# 16_-_PWR_2V5_1V5.net
KiCad netlist of a schematic drawn in Altium Designer
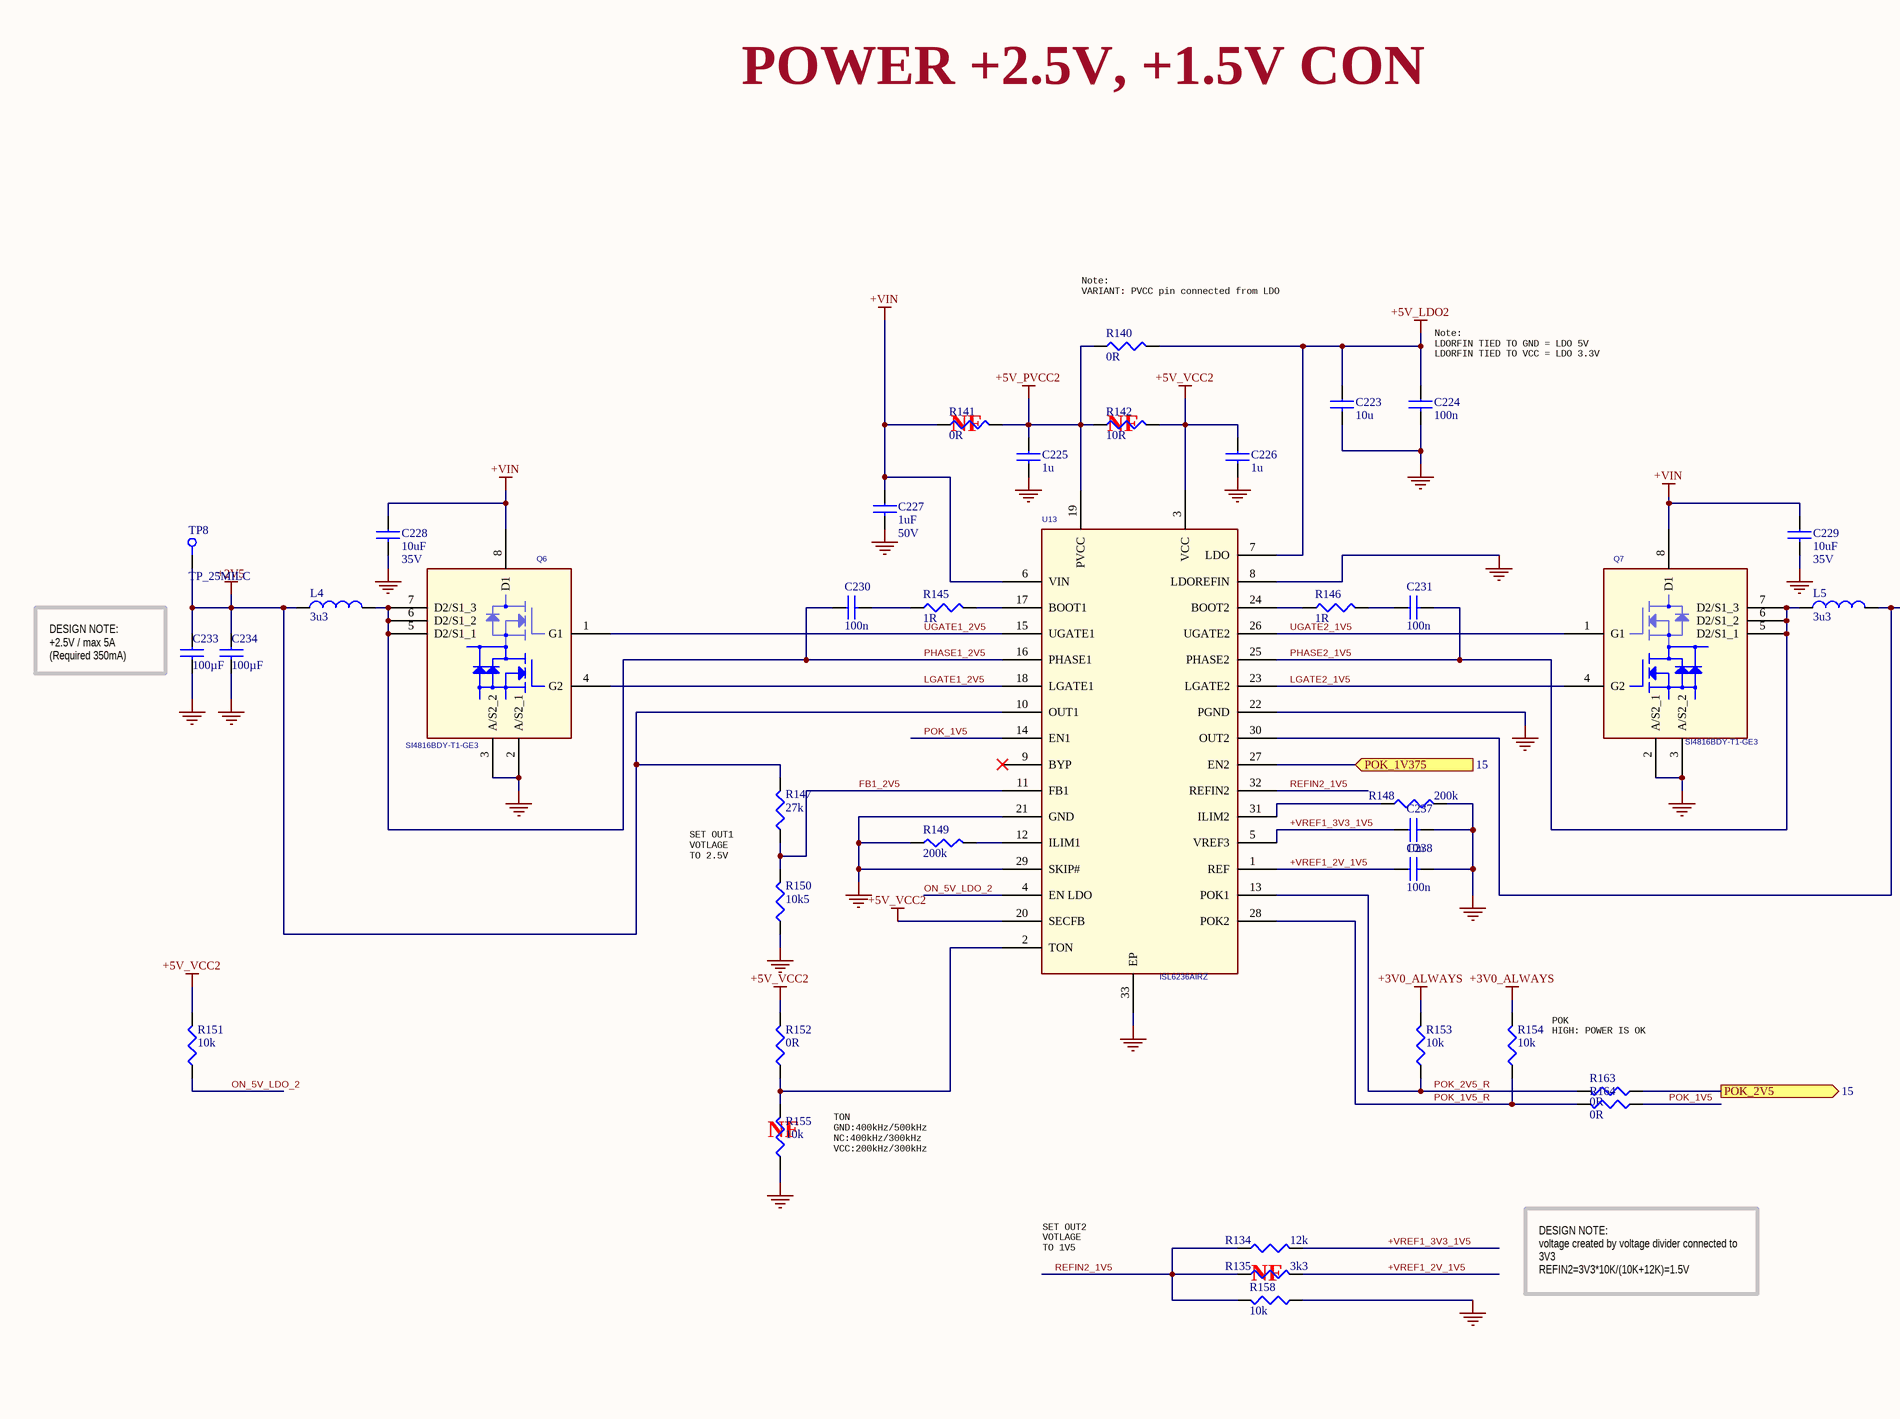
[diagram p0: [16] - PWR 2V5, 1V5.SchDoc, left]
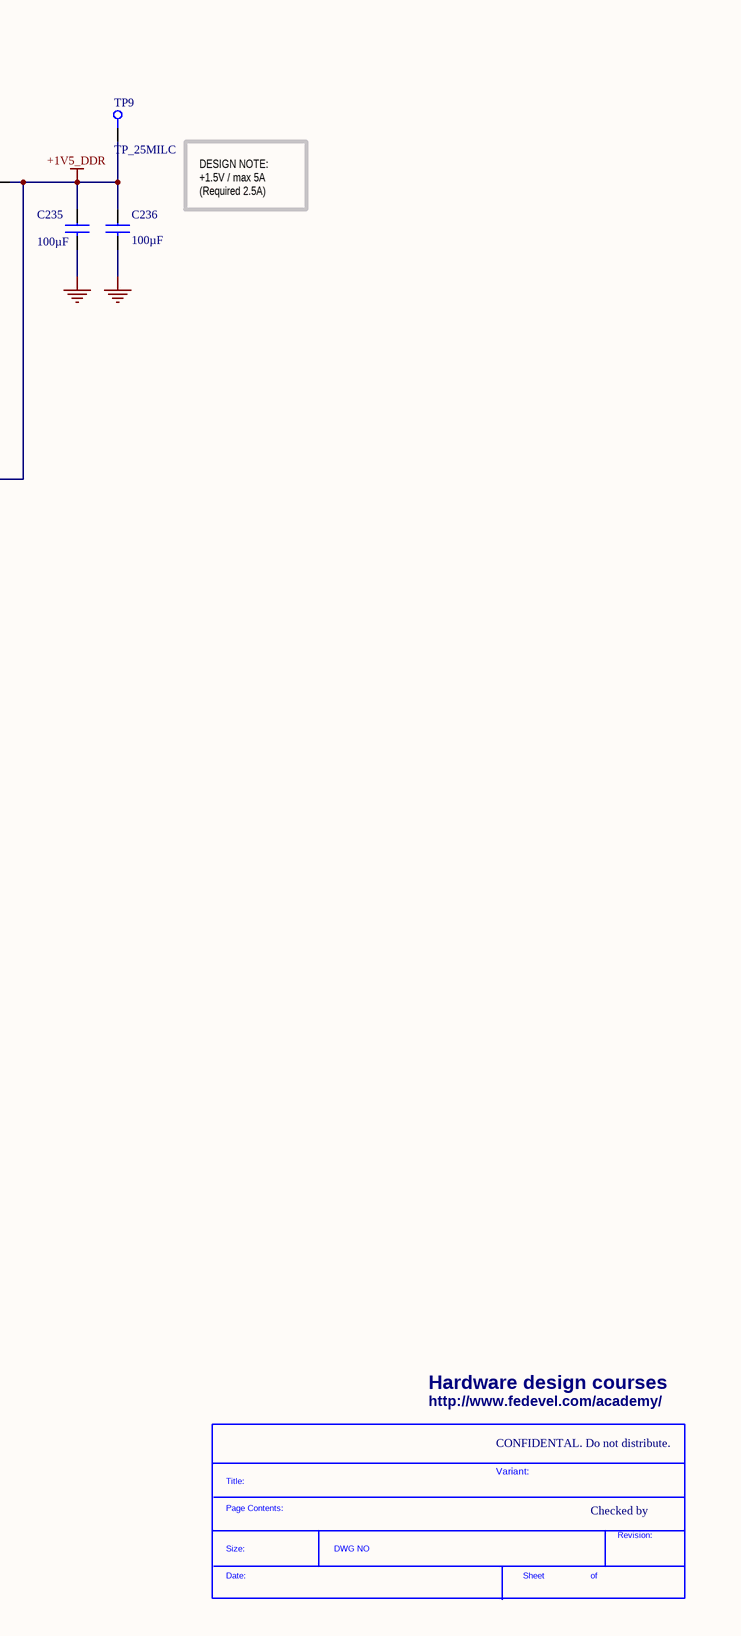
[diagram p1: [16] - PWR 2V5, 1V5.SchDoc, right]

(export (version "E")
  (design (tool "Eeschema 10.0.6"))
  (components
    (comp (ref "C223")
      (value "10u")
      (footprint "C0603")
      (description "CAP CER 10UF 6.3V X5R 20% 0603")
      (fields
        (field (name "MANUFACTURER") "TDK Corporation")
        (field (name "MANUFACTURER PART NUMBER") "C1608X5R0J106M")
      )
      (libsource (lib "iMX6 Rex_V1I1") (part "C1608X5R0J106M"))
    )
    (comp (ref "C224")
      (value "100n")
      (footprint "C0402")
      (description "CAP CER .10UF 50V X5R 10% 0402")
      (fields
        (field (name "MANUFACTURER") "TDK Corporation")
        (field (name "MANUFACTURER PART NUMBER") "C1005X5R1H104K")
      )
      (libsource (lib "iMX6 Rex_V1I1") (part "C1005X5R1H104K"))
    )
    (comp (ref "C225")
      (value "1u")
      (footprint "C0402")
      (description "CAP CER 1.0UF 16V X5R 0402")
      (fields
        (field (name "MANUFACTURER") "TDK Corporation")
        (field (name "MANUFACTURER PART NUMBER") "C1005X5R1C105K")
      )
      (libsource (lib "iMX6 Rex_V1I1") (part "C1005X5R1C105K"))
    )
    (comp (ref "C226")
      (value "1u")
      (footprint "C0402")
      (description "CAP CER 1.0UF 16V X5R 0402")
      (fields
        (field (name "MANUFACTURER") "TDK Corporation")
        (field (name "MANUFACTURER PART NUMBER") "C1005X5R1C105K")
      )
      (libsource (lib "iMX6 Rex_V1I1") (part "C1005X5R1C105K"))
    )
    (comp (ref "C227")
      (value "1uF")
      (footprint "C0805")
      (description "CAP CER 1UF 50V X7R 0805")
      (fields
        (field (name "MANUFACTURER") "Murata Electronics North America")
        (field (name "MANUFACTURER PART NUMBER") "GRM21BR71H105KA12L")
        (field (name "VOLTAGE - RATED") "50V")
      )
      (libsource (lib "iMX6 Rex_V1I1") (part "GRM21BR71H105KA12L"))
    )
    (comp (ref "C228")
      (value "10uF")
      (footprint "C1206")
      (description "CAP CER 10UF 35V X5R 1206")
      (fields
        (field (name "MANUFACTURER") "Murata Electronics North America")
        (field (name "MANUFACTURER PART NUMBER") "GRM31CR6YA106KA12L")
        (field (name "VOLTAGE - RATED") "35V")
      )
      (libsource (lib "iMX6 Rex_V1I1") (part "GRM31CR6YA106KA12L"))
    )
    (comp (ref "C229")
      (value "10uF")
      (footprint "C1206")
      (description "CAP CER 10UF 35V X5R 1206")
      (fields
        (field (name "MANUFACTURER") "Murata Electronics North America")
        (field (name "MANUFACTURER PART NUMBER") "GRM31CR6YA106KA12L")
        (field (name "VOLTAGE - RATED") "35V")
      )
      (libsource (lib "iMX6 Rex_V1I1") (part "GRM31CR6YA106KA12L"))
    )
    (comp (ref "C230")
      (value "100n")
      (footprint "C0402")
      (description "CAP CER .10UF 50V X5R 10% 0402")
      (fields
        (field (name "MANUFACTURER") "TDK Corporation")
        (field (name "MANUFACTURER PART NUMBER") "C1005X5R1H104K")
      )
      (libsource (lib "iMX6 Rex_V1I1") (part "C1005X5R1H104K"))
    )
    (comp (ref "C231")
      (value "100n")
      (footprint "C0402")
      (description "CAP CER .10UF 50V X5R 10% 0402")
      (fields
        (field (name "MANUFACTURER") "TDK Corporation")
        (field (name "MANUFACTURER PART NUMBER") "C1005X5R1H104K")
      )
      (libsource (lib "iMX6 Rex_V1I1") (part "C1005X5R1H104K"))
    )
    (comp (ref "C233")
      (value "100µF")
      (footprint "C1206")
      (description "CAP CER 100UF 10V X5R 20% 1206")
      (fields
        (field (name "MANUFACTURER") "TDK Corporation")
        (field (name "MANUFACTURER PART NUMBER") "C3216X5R1A107M")
      )
      (libsource (lib "iMX6 Rex_V1I1") (part "C3216X5R1A107M"))
    )
    (comp (ref "C234")
      (value "100µF")
      (footprint "C1206")
      (description "CAP CER 100UF 10V X5R 20% 1206")
      (fields
        (field (name "MANUFACTURER") "TDK Corporation")
        (field (name "MANUFACTURER PART NUMBER") "C3216X5R1A107M")
      )
      (libsource (lib "iMX6 Rex_V1I1") (part "C3216X5R1A107M"))
    )
    (comp (ref "C235")
      (value "100µF")
      (footprint "C1206")
      (description "CAP CER 100UF 10V X5R 20% 1206")
      (fields
        (field (name "MANUFACTURER") "TDK Corporation")
        (field (name "MANUFACTURER PART NUMBER") "C3216X5R1A107M")
      )
      (libsource (lib "iMX6 Rex_V1I1") (part "C3216X5R1A107M"))
    )
    (comp (ref "C236")
      (value "100µF")
      (footprint "C1206")
      (description "CAP CER 100UF 10V X5R 20% 1206")
      (fields
        (field (name "MANUFACTURER") "TDK Corporation")
        (field (name "MANUFACTURER PART NUMBER") "C3216X5R1A107M")
      )
      (libsource (lib "iMX6 Rex_V1I1") (part "C3216X5R1A107M"))
    )
    (comp (ref "C237")
      (value "10n")
      (footprint "C0402")
      (description "CAP CER 10000PF 16V X7R 10% 0402")
      (fields
        (field (name "MANUFACTURER") "TDK Corporation")
        (field (name "MANUFACTURER PART NUMBER") "C1005X7R1C103K")
      )
      (libsource (lib "iMX6 Rex_V1I1") (part "C1005X7R1C103K"))
    )
    (comp (ref "C238")
      (value "100n")
      (footprint "C0402")
      (description "CAP CER .10UF 50V X5R 10% 0402")
      (fields
        (field (name "MANUFACTURER") "TDK Corporation")
        (field (name "MANUFACTURER PART NUMBER") "C1005X5R1H104K")
      )
      (libsource (lib "iMX6 Rex_V1I1") (part "C1005X5R1H104K"))
    )
    (comp (ref "L4")
      (value "3u3")
      (footprint "IHLP_255MILx270MIL")
      (description "INDUCTOR POWER 3.3UH 6A SMD")
      (fields
        (field (name "MANUFACTURER") "Vishay Dale")
        (field (name "MANUFACTURER PART NUMBER") "IHLP2525CZER3R3M01")
        (field (name ".CHECKED PCB") "RF")
        (field (name ".CHECKED SCH") "RF")
      )
      (libsource (lib "iMX6 Rex_V1I1") (part "IHLP2525CZER3R3M01"))
    )
    (comp (ref "L5")
      (value "3u3")
      (footprint "IHLP_255MILx270MIL")
      (description "INDUCTOR POWER 3.3UH 6A SMD")
      (fields
        (field (name "MANUFACTURER") "Vishay Dale")
        (field (name "MANUFACTURER PART NUMBER") "IHLP2525CZER3R3M01")
        (field (name ".CHECKED PCB") "RF")
        (field (name ".CHECKED SCH") "RF")
      )
      (libsource (lib "iMX6 Rex_V1I1") (part "IHLP2525CZER3R3M01"))
    )
    (comp (ref "Q6")
      (value "SI4816BDY-T1-GE3")
      (footprint "8_SOIC_3.9MM")
      (description "MOSFET DL N-CH 30V 6.8A 8-SOIC")
      (fields (field (name "MANUFACTURER") "Vishay/Siliconix"))
      (libsource (lib "iMX6 Rex_V1I1") (part "SI4816BDY-T1-GE3"))
    )
    (comp (ref "Q7")
      (value "SI4816BDY-T1-GE3")
      (footprint "8_SOIC_3.9MM")
      (description "MOSFET DL N-CH 30V 6.8A 8-SOIC")
      (fields (field (name "MANUFACTURER") "Vishay/Siliconix"))
      (libsource (lib "iMX6 Rex_V1I1") (part "SI4816BDY-T1-GE3"))
    )
    (comp (ref "R134")
      (value "12k")
      (footprint "R0402")
      (description "RES 12.0K OHM 1/16W 1% 0402 SMD")
      (fields
        (field (name "MANUFACTURER") "Yageo")
        (field (name "MANUFACTURER PART NUMBER") "RC0402FR-0712KL")
      )
      (libsource (lib "iMX6 Rex_V1I1") (part "RC0402FR-0712KL"))
    )
    (comp (ref "R135")
      (value "3k3")
      (footprint "R0402")
      (description "RES 3.30K OHM 1/16W 1% 0402 SMD")
      (fields
        (field (name "MANUFACTURER") "Yageo")
        (field (name "MANUFACTURER PART NUMBER") "RC0402FR-073K3L")
      )
      (libsource (lib "iMX6 Rex_V1I1") (part "RC0402FR-073K3L"))
    )
    (comp (ref "R140")
      (value "0R")
      (footprint "R0402")
      (description "RES 0.0 OHM 1/16W 0402 SMD")
      (fields
        (field (name "MANUFACTURER") "Yageo")
        (field (name "MANUFACTURER PART NUMBER") "RC0402JR-070RL")
      )
      (libsource (lib "iMX6 Rex_V1I1") (part "RC0402JR-070RL"))
    )
    (comp (ref "R141")
      (value "0R")
      (footprint "R0402")
      (description "RES 0.0 OHM 1/16W 0402 SMD")
      (fields
        (field (name "MANUFACTURER") "Yageo")
        (field (name "MANUFACTURER PART NUMBER") "RC0402JR-070RL")
      )
      (libsource (lib "iMX6 Rex_V1I1") (part "RC0402JR-070RL"))
    )
    (comp (ref "R142")
      (value "10R")
      (footprint "R0402")
      (description "RES 10.0 OHM 1/16W 1% 0402 SMD")
      (fields
        (field (name "MANUFACTURER") "Yageo")
        (field (name "MANUFACTURER PART NUMBER") "RC0402FR-0710RL")
      )
      (libsource (lib "iMX6 Rex_V1I1") (part "RC0402FR-0710RL"))
    )
    (comp (ref "R145")
      (value "1R")
      (footprint "R0402")
      (description "RES 1.00 OHM 1/16W 1% 0402 SM")
      (fields
        (field (name "MANUFACTURER") "Yageo")
        (field (name "MANUFACTURER PART NUMBER") "RC0402FR-071RL")
      )
      (libsource (lib "iMX6 Rex_V1I1") (part "RC0402FR-071RL"))
    )
    (comp (ref "R146")
      (value "1R")
      (footprint "R0402")
      (description "RES 1.00 OHM 1/16W 1% 0402 SM")
      (fields
        (field (name "MANUFACTURER") "Yageo")
        (field (name "MANUFACTURER PART NUMBER") "RC0402FR-071RL")
      )
      (libsource (lib "iMX6 Rex_V1I1") (part "RC0402FR-071RL"))
    )
    (comp (ref "R147")
      (value "27k")
      (footprint "R0402")
      (description "RES 27.0K OHM 1/16W 1% 0402 SMD")
      (fields
        (field (name "MANUFACTURER") "Yageo")
        (field (name "MANUFACTURER PART NUMBER") "RC0402FR-0727KL")
        (field (name ".CHECKED PCB") "RF")
        (field (name ".CHECKED SCH") "RF")
      )
      (libsource (lib "iMX6 Rex_V1I1") (part "RC0402FR-0727KL"))
    )
    (comp (ref "R148")
      (value "200k")
      (footprint "R0402")
      (description "RES 200K OHM 1/16W 1% 0402 SMD")
      (fields
        (field (name "MANUFACTURER") "Yageo")
        (field (name "MANUFACTURER PART NUMBER") "RC0402FR-07200KL")
      )
      (libsource (lib "iMX6 Rex_V1I1") (part "RC0402FR-07200KL"))
    )
    (comp (ref "R149")
      (value "200k")
      (footprint "R0402")
      (description "RES 200K OHM 1/16W 1% 0402 SMD")
      (fields
        (field (name "MANUFACTURER") "Yageo")
        (field (name "MANUFACTURER PART NUMBER") "RC0402FR-07200KL")
      )
      (libsource (lib "iMX6 Rex_V1I1") (part "RC0402FR-07200KL"))
    )
    (comp (ref "R150")
      (value "10k5")
      (footprint "R0402")
      (description "RES 10.5K OHM 1/16W 1% 0402 SMD")
      (fields
        (field (name "MANUFACTURER") "Vishay/Dale")
        (field (name "MANUFACTURER PART NUMBER") "CRCW040210K5FKED")
      )
      (libsource (lib "iMX6 Rex_V1I1") (part "CRCW040210K5FKED"))
    )
    (comp (ref "R151")
      (value "10k")
      (footprint "R0402")
      (description "RES 10.0K OHM 1/16W 1% 0402 SMD")
      (fields
        (field (name "MANUFACTURER") "Yageo")
        (field (name "MANUFACTURER PART NUMBER") "RC0402FR-0710KL")
      )
      (libsource (lib "iMX6 Rex_V1I1") (part "RC0402FR-0710KL"))
    )
    (comp (ref "R152")
      (value "0R")
      (footprint "R0402")
      (description "RES 0.0 OHM 1/16W 0402 SMD")
      (fields
        (field (name "MANUFACTURER") "Yageo")
        (field (name "MANUFACTURER PART NUMBER") "RC0402JR-070RL")
      )
      (libsource (lib "iMX6 Rex_V1I1") (part "RC0402JR-070RL"))
    )
    (comp (ref "R153")
      (value "10k")
      (footprint "R0402")
      (description "RES 10.0K OHM 1/16W 1% 0402 SMD")
      (fields
        (field (name "MANUFACTURER") "Yageo")
        (field (name "MANUFACTURER PART NUMBER") "RC0402FR-0710KL")
      )
      (libsource (lib "iMX6 Rex_V1I1") (part "RC0402FR-0710KL"))
    )
    (comp (ref "R154")
      (value "10k")
      (footprint "R0402")
      (description "RES 10.0K OHM 1/16W 1% 0402 SMD")
      (fields
        (field (name "MANUFACTURER") "Yageo")
        (field (name "MANUFACTURER PART NUMBER") "RC0402FR-0710KL")
      )
      (libsource (lib "iMX6 Rex_V1I1") (part "RC0402FR-0710KL"))
    )
    (comp (ref "R155")
      (value "10k")
      (footprint "R0402")
      (description "RES 10.0K OHM 1/16W 1% 0402 SMD")
      (fields
        (field (name "MANUFACTURER") "Yageo")
        (field (name "MANUFACTURER PART NUMBER") "RC0402FR-0710KL")
      )
      (libsource (lib "iMX6 Rex_V1I1") (part "RC0402FR-0710KL"))
    )
    (comp (ref "R158")
      (value "10k")
      (footprint "R0402")
      (description "RES 10.0K OHM 1/16W 1% 0402 SMD")
      (fields
        (field (name "MANUFACTURER") "Yageo")
        (field (name "MANUFACTURER PART NUMBER") "RC0402FR-0710KL")
      )
      (libsource (lib "iMX6 Rex_V1I1") (part "RC0402FR-0710KL"))
    )
    (comp (ref "R163")
      (value "0R")
      (footprint "R0402")
      (description "RES 0.0 OHM 1/16W 0402 SMD")
      (fields
        (field (name "MANUFACTURER") "Yageo")
        (field (name "MANUFACTURER PART NUMBER") "RC0402JR-070RL")
      )
      (libsource (lib "iMX6 Rex_V1I1") (part "RC0402JR-070RL"))
    )
    (comp (ref "R164")
      (value "0R")
      (footprint "R0402")
      (description "RES 0.0 OHM 1/16W 0402 SMD")
      (fields
        (field (name "MANUFACTURER") "Yageo")
        (field (name "MANUFACTURER PART NUMBER") "RC0402JR-070RL")
      )
      (libsource (lib "iMX6 Rex_V1I1") (part "RC0402JR-070RL"))
    )
    (comp (ref "TP8")
      (value "TP_25MILC")
      (footprint "TP_25C")
      (description "Test Point 25mil")
      (libsource (lib "iMX6 Rex_V1I1") (part "TP_25MILC"))
    )
    (comp (ref "TP9")
      (value "TP_25MILC")
      (footprint "TP_25C")
      (description "Test Point 25mil")
      (libsource (lib "iMX6 Rex_V1I1") (part "TP_25MILC"))
    )
    (comp (ref "U13")
      (value "ISL6236AIRZ")
      (footprint "32_VFQFN_EXPOSED_PAD")
      (description "IC MAIN PWR CTRLR QUAD 32-QFN")
      (fields (field (name "MANUFACTURER") "Intersil"))
      (libsource (lib "iMX6 Rex_V1I1") (part "ISL6236AIRZ"))
    )
  )
  (nets
    (net (code "1") (name "+1V5_DDR") (class "Default")
      (node (ref "C235") (pin "1") (pinfunction "1_1") (pintype "passive"))
      (node (ref "C236") (pin "1") (pinfunction "1_1") (pintype "passive"))
      (node (ref "L5") (pin "2") (pinfunction "2_2") (pintype "passive"))
      (node (ref "TP9") (pin "1") (pinfunction "1_1") (pintype "passive"))
      (node (ref "U13") (pin "30") (pinfunction "OUT2_30") (pintype "passive"))
    )
    (net (code "2") (name "+2V5") (class "Default")
      (node (ref "C233") (pin "1") (pinfunction "1_1") (pintype "passive"))
      (node (ref "C234") (pin "1") (pinfunction "1_1") (pintype "passive"))
      (node (ref "L4") (pin "1") (pinfunction "1_1") (pintype "passive"))
      (node (ref "R147") (pin "2") (pinfunction "2_2") (pintype "passive"))
      (node (ref "TP8") (pin "1") (pinfunction "1_1") (pintype "passive"))
      (node (ref "U13") (pin "10") (pinfunction "OUT1_10") (pintype "passive"))
    )
    (net (code "3") (name "+3V0_ALWAYS") (class "Default")
      (node (ref "R153") (pin "2") (pinfunction "2_2") (pintype "passive"))
      (node (ref "R154") (pin "2") (pinfunction "2_2") (pintype "passive"))
    )
    (net (code "4") (name "+5V_LDO2") (class "Default")
      (node (ref "C223") (pin "1") (pinfunction "1_1") (pintype "passive"))
      (node (ref "C224") (pin "1") (pinfunction "1_1") (pintype "passive"))
      (node (ref "R140") (pin "2") (pinfunction "2_2") (pintype "passive"))
      (node (ref "U13") (pin "7") (pinfunction "LDO_7") (pintype "passive"))
    )
    (net (code "5") (name "+5V_PVCC2") (class "Default")
      (node (ref "C225") (pin "1") (pinfunction "1_1") (pintype "passive"))
      (node (ref "R140") (pin "1") (pinfunction "1_1") (pintype "passive"))
      (node (ref "R141") (pin "2") (pinfunction "2_2") (pintype "passive"))
      (node (ref "R142") (pin "1") (pinfunction "1_1") (pintype "passive"))
      (node (ref "U13") (pin "19") (pinfunction "PVCC_19") (pintype "passive"))
    )
    (net (code "6") (name "+5V_VCC2") (class "Default")
      (node (ref "C226") (pin "1") (pinfunction "1_1") (pintype "passive"))
      (node (ref "R142") (pin "2") (pinfunction "2_2") (pintype "passive"))
      (node (ref "R151") (pin "2") (pinfunction "2_2") (pintype "passive"))
      (node (ref "R152") (pin "2") (pinfunction "2_2") (pintype "passive"))
      (node (ref "U13") (pin "20") (pinfunction "SECFB_20") (pintype "passive"))
      (node (ref "U13") (pin "3") (pinfunction "VCC_3") (pintype "passive"))
    )
    (net (code "7") (name "+VIN") (class "Default")
      (node (ref "C227") (pin "1") (pinfunction "1_1") (pintype "passive"))
      (node (ref "C228") (pin "1") (pinfunction "1_1") (pintype "passive"))
      (node (ref "C229") (pin "1") (pinfunction "1_1") (pintype "passive"))
      (node (ref "Q6") (pin "8") (pinfunction "D1_8") (pintype "passive"))
      (node (ref "Q7") (pin "8") (pinfunction "D1_8") (pintype "passive"))
      (node (ref "R141") (pin "1") (pinfunction "1_1") (pintype "passive"))
      (node (ref "U13") (pin "6") (pinfunction "VIN_6") (pintype "passive"))
    )
    (net (code "8") (name "/+VREF1_2V_1V5") (class "Default")
      (node (ref "C238") (pin "1") (pinfunction "1_1") (pintype "passive"))
      (node (ref "R135") (pin "2") (pinfunction "2_2") (pintype "passive"))
      (node (ref "U13") (pin "1") (pinfunction "REF_1") (pintype "passive"))
    )
    (net (code "9") (name "/+VREF1_3V3_1V5") (class "Default")
      (node (ref "C237") (pin "1") (pinfunction "1_1") (pintype "passive"))
      (node (ref "R134") (pin "2") (pinfunction "2_2") (pintype "passive"))
      (node (ref "U13") (pin "5") (pinfunction "VREF3_5") (pintype "passive"))
    )
    (net (code "10") (name "/FB1_2V5") (class "Default")
      (node (ref "R147") (pin "1") (pinfunction "1_1") (pintype "passive"))
      (node (ref "R150") (pin "2") (pinfunction "2_2") (pintype "passive"))
      (node (ref "U13") (pin "11") (pinfunction "FB1_11") (pintype "passive"))
    )
    (net (code "11") (name "/LGATE1_2V5") (class "Default")
      (node (ref "Q6") (pin "4") (pinfunction "G2_4") (pintype "passive"))
      (node (ref "U13") (pin "18") (pinfunction "LGATE1_18") (pintype "passive"))
    )
    (net (code "12") (name "/LGATE2_1V5") (class "Default")
      (node (ref "Q7") (pin "4") (pinfunction "G2_4") (pintype "passive"))
      (node (ref "U13") (pin "23") (pinfunction "LGATE2_23") (pintype "passive"))
    )
    (net (code "13") (name "/ON_5V_LDO_2") (class "Default")
      (node (ref "R151") (pin "1") (pinfunction "1_1") (pintype "passive"))
      (node (ref "U13") (pin "4") (pinfunction "EN_LDO_4") (pintype "passive"))
    )
    (net (code "14") (name "/PHASE1_2V5") (class "Default")
      (node (ref "C230") (pin "1") (pinfunction "1_1") (pintype "passive"))
      (node (ref "L4") (pin "2") (pinfunction "2_2") (pintype "passive"))
      (node (ref "Q6") (pin "5") (pinfunction "D2/S1_1_5") (pintype "passive"))
      (node (ref "Q6") (pin "6") (pinfunction "D2/S1_2_6") (pintype "passive"))
      (node (ref "Q6") (pin "7") (pinfunction "D2/S1_3_7") (pintype "passive"))
      (node (ref "U13") (pin "16") (pinfunction "PHASE1_16") (pintype "passive"))
    )
    (net (code "15") (name "/PHASE2_1V5") (class "Default")
      (node (ref "C231") (pin "2") (pinfunction "2_2") (pintype "passive"))
      (node (ref "L5") (pin "1") (pinfunction "1_1") (pintype "passive"))
      (node (ref "Q7") (pin "5") (pinfunction "D2/S1_1_5") (pintype "passive"))
      (node (ref "Q7") (pin "6") (pinfunction "D2/S1_2_6") (pintype "passive"))
      (node (ref "Q7") (pin "7") (pinfunction "D2/S1_3_7") (pintype "passive"))
      (node (ref "U13") (pin "25") (pinfunction "PHASE2_25") (pintype "passive"))
    )
    (net (code "16") (name "/POK_1V5") (class "Default")
      (node (ref "R164") (pin "1") (pinfunction "1_1") (pintype "passive"))
      (node (ref "U13") (pin "14") (pinfunction "EN1_14") (pintype "passive"))
    )
    (net (code "17") (name "/POK_1V5_R") (class "Default")
      (node (ref "R154") (pin "1") (pinfunction "1_1") (pintype "passive"))
      (node (ref "R164") (pin "2") (pinfunction "2_2") (pintype "passive"))
      (node (ref "U13") (pin "28") (pinfunction "POK2_28") (pintype "passive"))
    )
    (net (code "18") (name "/POK_1V375") (class "Default")
      (node (ref "U13") (pin "27") (pinfunction "EN2_27") (pintype "passive"))
    )
    (net (code "19") (name "/POK_2V5") (class "Default")
      (node (ref "R163") (pin "1") (pinfunction "1_1") (pintype "passive"))
    )
    (net (code "20") (name "/POK_2V5_R") (class "Default")
      (node (ref "R153") (pin "1") (pinfunction "1_1") (pintype "passive"))
      (node (ref "R163") (pin "2") (pinfunction "2_2") (pintype "passive"))
      (node (ref "U13") (pin "13") (pinfunction "POK1_13") (pintype "passive"))
    )
    (net (code "21") (name "/REFIN2_1V5") (class "Default")
      (node (ref "R134") (pin "1") (pinfunction "1_1") (pintype "passive"))
      (node (ref "R135") (pin "1") (pinfunction "1_1") (pintype "passive"))
      (node (ref "R158") (pin "2") (pinfunction "2_2") (pintype "passive"))
      (node (ref "U13") (pin "32") (pinfunction "REFIN2_32") (pintype "passive"))
    )
    (net (code "22") (name "/UGATE1_2V5") (class "Default")
      (node (ref "Q6") (pin "1") (pinfunction "G1_1") (pintype "passive"))
      (node (ref "U13") (pin "15") (pinfunction "UGATE1_15") (pintype "passive"))
    )
    (net (code "23") (name "/UGATE2_1V5") (class "Default")
      (node (ref "Q7") (pin "1") (pinfunction "G1_1") (pintype "passive"))
      (node (ref "U13") (pin "26") (pinfunction "UGATE2_26") (pintype "passive"))
    )
    (net (code "24") (name "GND") (class "Default")
      (node (ref "C223") (pin "2") (pinfunction "2_2") (pintype "passive"))
      (node (ref "C224") (pin "2") (pinfunction "2_2") (pintype "passive"))
      (node (ref "C225") (pin "2") (pinfunction "2_2") (pintype "passive"))
      (node (ref "C226") (pin "2") (pinfunction "2_2") (pintype "passive"))
      (node (ref "C227") (pin "2") (pinfunction "2_2") (pintype "passive"))
      (node (ref "C228") (pin "2") (pinfunction "2_2") (pintype "passive"))
      (node (ref "C229") (pin "2") (pinfunction "2_2") (pintype "passive"))
      (node (ref "C233") (pin "2") (pinfunction "2_2") (pintype "passive"))
      (node (ref "C234") (pin "2") (pinfunction "2_2") (pintype "passive"))
      (node (ref "C235") (pin "2") (pinfunction "2_2") (pintype "passive"))
      (node (ref "C236") (pin "2") (pinfunction "2_2") (pintype "passive"))
      (node (ref "C237") (pin "2") (pinfunction "2_2") (pintype "passive"))
      (node (ref "C238") (pin "2") (pinfunction "2_2") (pintype "passive"))
      (node (ref "Q6") (pin "2") (pinfunction "A/S2_1_2") (pintype "passive"))
      (node (ref "Q6") (pin "3") (pinfunction "A/S2_2_3") (pintype "passive"))
      (node (ref "Q7") (pin "2") (pinfunction "A/S2_1_2") (pintype "passive"))
      (node (ref "Q7") (pin "3") (pinfunction "A/S2_2_3") (pintype "passive"))
      (node (ref "R148") (pin "2") (pinfunction "2_2") (pintype "passive"))
      (node (ref "R149") (pin "1") (pinfunction "1_1") (pintype "passive"))
      (node (ref "R150") (pin "1") (pinfunction "1_1") (pintype "passive"))
      (node (ref "R155") (pin "1") (pinfunction "1_1") (pintype "passive"))
      (node (ref "R158") (pin "1") (pinfunction "1_1") (pintype "passive"))
      (node (ref "U13") (pin "21") (pinfunction "GND_21") (pintype "passive"))
      (node (ref "U13") (pin "22") (pinfunction "PGND_22") (pintype "passive"))
      (node (ref "U13") (pin "29") (pinfunction "SKIP#_29") (pintype "passive"))
      (node (ref "U13") (pin "33") (pinfunction "EP_33") (pintype "passive"))
      (node (ref "U13") (pin "8") (pinfunction "LDOREFIN_8") (pintype "passive"))
    )
    (net (code "25") (name "Net-(C230-Pad2)") (class "Default")
      (node (ref "C230") (pin "2") (pinfunction "2_2") (pintype "passive"))
      (node (ref "R145") (pin "1") (pinfunction "1_1") (pintype "passive"))
    )
    (net (code "26") (name "Net-(C231-Pad1)") (class "Default")
      (node (ref "C231") (pin "1") (pinfunction "1_1") (pintype "passive"))
      (node (ref "R146") (pin "2") (pinfunction "2_2") (pintype "passive"))
    )
    (net (code "27") (name "Net-(U13-BOOT1)") (class "Default")
      (node (ref "R145") (pin "2") (pinfunction "2_2") (pintype "passive"))
      (node (ref "U13") (pin "17") (pinfunction "BOOT1_17") (pintype "passive"))
    )
    (net (code "28") (name "Net-(U13-BOOT2)") (class "Default")
      (node (ref "R146") (pin "1") (pinfunction "1_1") (pintype "passive"))
      (node (ref "U13") (pin "24") (pinfunction "BOOT2_24") (pintype "passive"))
    )
    (net (code "29") (name "Net-(U13-ILIM1)") (class "Default")
      (node (ref "R149") (pin "2") (pinfunction "2_2") (pintype "passive"))
      (node (ref "U13") (pin "12") (pinfunction "ILIM1_12") (pintype "passive"))
    )
    (net (code "30") (name "Net-(U13-ILIM2)") (class "Default")
      (node (ref "R148") (pin "1") (pinfunction "1_1") (pintype "passive"))
      (node (ref "U13") (pin "31") (pinfunction "ILIM2_31") (pintype "passive"))
    )
    (net (code "31") (name "Net-(U13-TON)") (class "Default")
      (node (ref "R152") (pin "1") (pinfunction "1_1") (pintype "passive"))
      (node (ref "R155") (pin "2") (pinfunction "2_2") (pintype "passive"))
      (node (ref "U13") (pin "2") (pinfunction "TON_2") (pintype "passive"))
    )
    (net (code "32") (name "unconnected-(U13-BYP-Pad9)") (class "Default")
      (node (ref "U13") (pin "9") (pinfunction "BYP_9") (pintype "passive+no_connect"))
    )
  )
)
